# Kilobot_Controller_ISP.net
KiCad netlist of a schematic drawn in Altium Designer
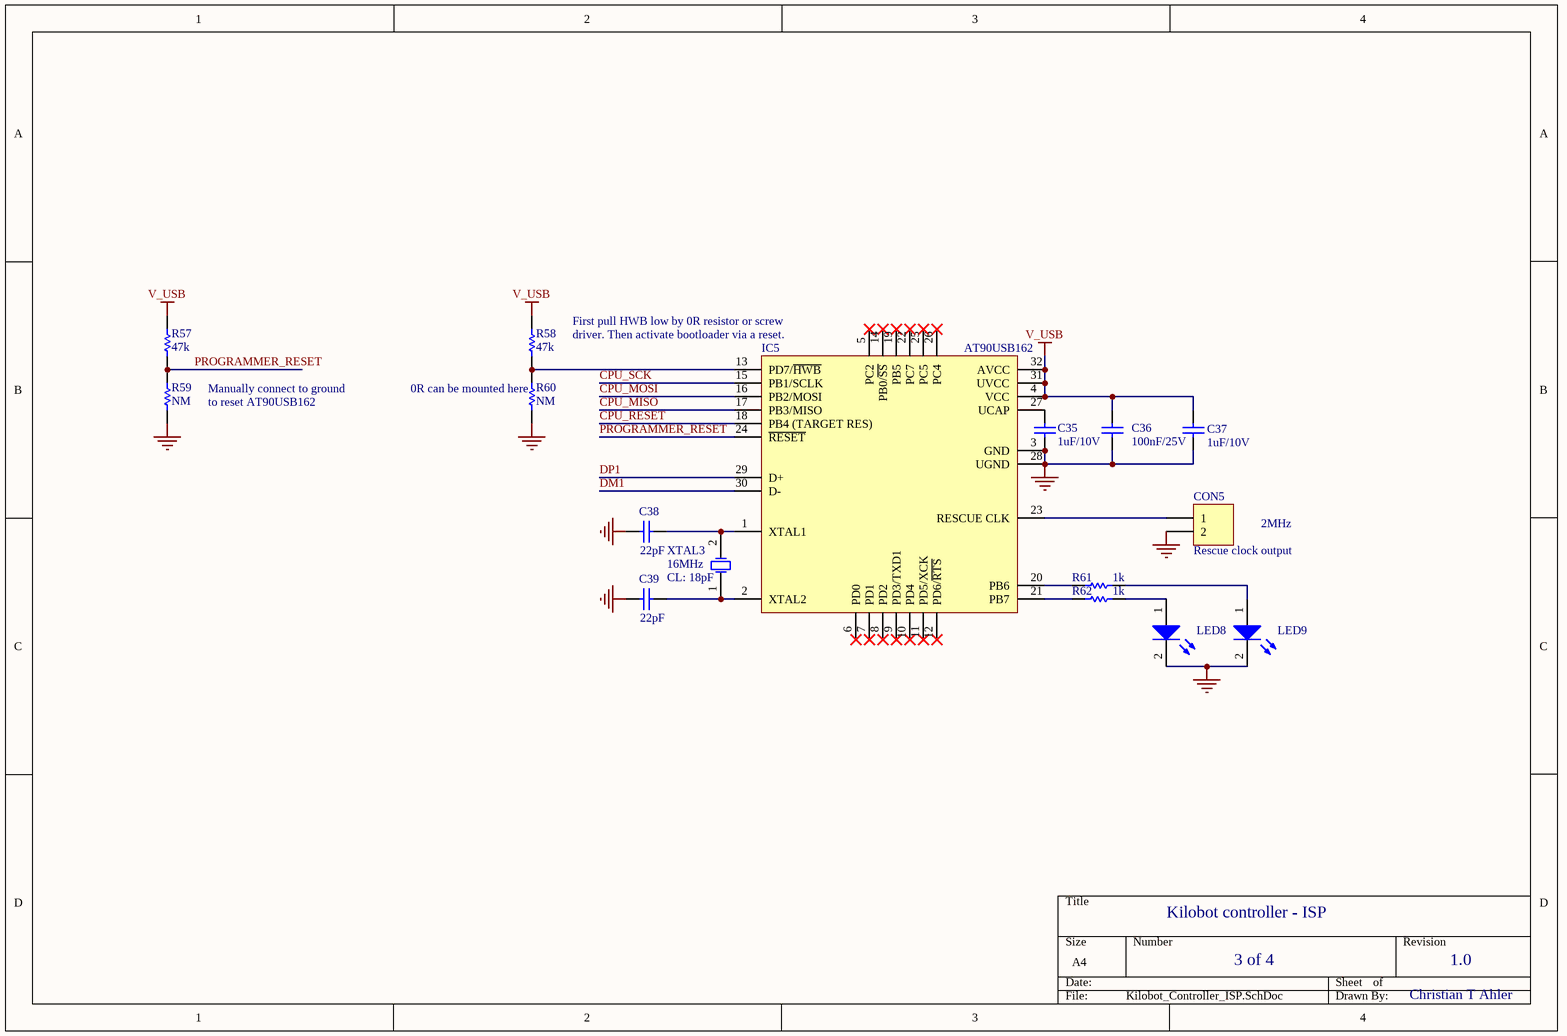
[diagram p0: Kilobot_Controller_ISP.SchDoc]

(export (version "E")
  (design (tool "Eeschema 10.0.6"))
  (components
    (comp (ref "C35")
      (value "1uF/10V")
      (footprint "RESC1608L")
      (description "Ceramic Chip Capacitor - Standard")
      (fields (field (name "Comment") "C0603"))
      (libsource (lib "KEMET Chip Capacitor") (part "C0603"))
    )
    (comp (ref "C36")
      (value "100nF/25V")
      (footprint "RESC1608L")
      (description "Ceramic Chip Capacitor - Standard")
      (fields (field (name "Comment") "C0603"))
      (libsource (lib "KEMET Chip Capacitor") (part "C0603"))
    )
    (comp (ref "C37")
      (value "1uF/10V")
      (footprint "RESC1608L")
      (description "Ceramic Chip Capacitor - Standard")
      (fields (field (name "Comment") "C0603"))
      (libsource (lib "KEMET Chip Capacitor") (part "C0603"))
    )
    (comp (ref "C38")
      (value "22pF")
      (footprint "RESC1608L")
      (description "Ceramic Chip Capacitor - Standard")
      (fields (field (name "Comment") "C0603"))
      (libsource (lib "KEMET Chip Capacitor") (part "C0603"))
    )
    (comp (ref "C39")
      (value "22pF")
      (footprint "RESC1608L")
      (description "Ceramic Chip Capacitor - Standard")
      (fields (field (name "Comment") "C0603"))
      (libsource (lib "KEMET Chip Capacitor") (part "C0603"))
    )
    (comp (ref "CON5")
      (value "Rescue clock output")
      (footprint "HDR1X2")
      (description "Header, 2-Pin")
      (libsource (lib "Miscellaneous Connectors") (part "Header 2"))
    )
    (comp (ref "IC5")
      (value "AT90USB162")
      (footprint "TQFP32")
      (libsource (lib "Kilobot_Controller") (part "AT90USB162"))
    )
    (comp (ref "LED8") (value "LED") (footprint "LED0603") (libsource (lib "KilobotCommercial") (part "LED")))
    (comp (ref "LED9") (value "LED") (footprint "LED0603") (libsource (lib "KilobotCommercial") (part "LED")))
    (comp (ref "R57")
      (value "47k")
      (footprint "RESC1608L")
      (description "Resistor")
      (fields (field (name "Comment") "Res1"))
      (libsource (lib "Miscellaneous Devices") (part "Res1"))
    )
    (comp (ref "R58")
      (value "47k")
      (footprint "RESC1608L")
      (description "Resistor")
      (fields (field (name "Comment") "Res1"))
      (libsource (lib "Miscellaneous Devices") (part "Res1"))
    )
    (comp (ref "R59")
      (value "NM")
      (footprint "RESC1608L")
      (description "Resistor")
      (fields (field (name "Comment") "Res1"))
      (libsource (lib "Miscellaneous Devices") (part "Res1"))
    )
    (comp (ref "R60")
      (value "NM")
      (footprint "RESC1608L")
      (description "Resistor")
      (fields (field (name "Comment") "Res1"))
      (libsource (lib "Miscellaneous Devices") (part "Res1"))
    )
    (comp (ref "R61")
      (value "1k")
      (footprint "RESC1608L")
      (description "Resistor")
      (fields (field (name "Comment") "Res1"))
      (libsource (lib "Miscellaneous Devices") (part "Res1"))
    )
    (comp (ref "R62")
      (value "1k")
      (footprint "RESC1608L")
      (description "Resistor")
      (fields (field (name "Comment") "Res1"))
      (libsource (lib "Miscellaneous Devices") (part "Res1"))
    )
    (comp (ref "XTAL3")
      (value "16MHz")
      (footprint "crystal-hc49")
      (fields (field (name "CL") "18pF") (field (name "Comment") "Crystal"))
      (libsource (lib "Programmer") (part "Crystal"))
    )
  )
  (nets
    (net (code "1") (name "/CPU_MISO") (class "Default")
      (node (ref "IC5") (pin "17") (pinfunction "PB3/MISO_17") (pintype "passive"))
    )
    (net (code "2") (name "/CPU_MOSI") (class "Default")
      (node (ref "IC5") (pin "16") (pinfunction "PB2/MOSI_16") (pintype "passive"))
    )
    (net (code "3") (name "/CPU_RESET") (class "Default")
      (node (ref "IC5") (pin "18") (pinfunction "PB4_(TARGET_RES)_18") (pintype "passive"))
    )
    (net (code "4") (name "/CPU_SCK") (class "Default")
      (node (ref "IC5") (pin "15") (pinfunction "PB1/SCLK_15") (pintype "passive"))
    )
    (net (code "5") (name "/DM1") (class "Default")
      (node (ref "IC5") (pin "30") (pinfunction "D-_30") (pintype "passive"))
    )
    (net (code "6") (name "/DP1") (class "Default")
      (node (ref "IC5") (pin "29") (pinfunction "D+_29") (pintype "passive"))
    )
    (net (code "7") (name "/PROGRAMMER_RESET") (class "Default")
      (node (ref "IC5") (pin "24") (pinfunction "~{RESET}_24") (pintype "passive"))
      (node (ref "R57") (pin "2") (pinfunction "2_2") (pintype "passive"))
      (node (ref "R59") (pin "1") (pinfunction "1_1") (pintype "passive"))
    )
    (net (code "8") (name "GND") (class "Default")
      (node (ref "C35") (pin "1") (pinfunction "1_1") (pintype "passive"))
      (node (ref "C36") (pin "2") (pinfunction "2_2") (pintype "passive"))
      (node (ref "C37") (pin "1") (pinfunction "1_1") (pintype "passive"))
      (node (ref "C38") (pin "1") (pinfunction "1_1") (pintype "passive"))
      (node (ref "C39") (pin "1") (pinfunction "1_1") (pintype "passive"))
      (node (ref "CON5") (pin "2") (pinfunction "2_2") (pintype "passive"))
      (node (ref "IC5") (pin "28") (pinfunction "UGND_28") (pintype "passive"))
      (node (ref "IC5") (pin "3") (pinfunction "GND_3") (pintype "passive"))
      (node (ref "LED8") (pin "2") (pinfunction "K_2") (pintype "passive"))
      (node (ref "LED9") (pin "2") (pinfunction "K_2") (pintype "passive"))
      (node (ref "R59") (pin "2") (pinfunction "2_2") (pintype "passive"))
      (node (ref "R60") (pin "2") (pinfunction "2_2") (pintype "passive"))
    )
    (net (code "9") (name "Net-(IC5-PB6)") (class "Default")
      (node (ref "IC5") (pin "20") (pinfunction "PB6_20") (pintype "passive"))
      (node (ref "R61") (pin "2") (pinfunction "2_2") (pintype "passive"))
    )
    (net (code "10") (name "Net-(IC5-PB7)") (class "Default")
      (node (ref "IC5") (pin "21") (pinfunction "PB7_21") (pintype "passive"))
      (node (ref "R62") (pin "2") (pinfunction "2_2") (pintype "passive"))
    )
    (net (code "11") (name "Net-(IC5-PD7{slash}~{HWB})") (class "Default")
      (node (ref "IC5") (pin "13") (pinfunction "PD7/~{HWB}_13") (pintype "passive"))
      (node (ref "R58") (pin "2") (pinfunction "2_2") (pintype "passive"))
      (node (ref "R60") (pin "1") (pinfunction "1_1") (pintype "passive"))
    )
    (net (code "12") (name "Net-(IC5-RESCUE_CLK)") (class "Default")
      (node (ref "CON5") (pin "1") (pinfunction "1_1") (pintype "passive"))
      (node (ref "IC5") (pin "23") (pinfunction "RESCUE_CLK_23") (pintype "passive"))
    )
    (net (code "13") (name "Net-(IC5-UCAP)") (class "Default")
      (node (ref "C35") (pin "2") (pinfunction "2_2") (pintype "passive"))
      (node (ref "IC5") (pin "27") (pinfunction "UCAP_27") (pintype "passive"))
    )
    (net (code "14") (name "Net-(IC5-XTAL1)") (class "Default")
      (node (ref "C38") (pin "2") (pinfunction "2_2") (pintype "passive"))
      (node (ref "IC5") (pin "1") (pinfunction "XTAL1_1") (pintype "passive"))
      (node (ref "XTAL3") (pin "2") (pinfunction "OSC2_2") (pintype "passive"))
    )
    (net (code "15") (name "Net-(IC5-XTAL2)") (class "Default")
      (node (ref "C39") (pin "2") (pinfunction "2_2") (pintype "passive"))
      (node (ref "IC5") (pin "2") (pinfunction "XTAL2_2") (pintype "passive"))
      (node (ref "XTAL3") (pin "1") (pinfunction "OSC1_1") (pintype "passive"))
    )
    (net (code "16") (name "Net-(LED8-A)") (class "Default")
      (node (ref "LED8") (pin "1") (pinfunction "A_1") (pintype "passive"))
      (node (ref "R62") (pin "1") (pinfunction "1_1") (pintype "passive"))
    )
    (net (code "17") (name "Net-(LED9-A)") (class "Default")
      (node (ref "LED9") (pin "1") (pinfunction "A_1") (pintype "passive"))
      (node (ref "R61") (pin "1") (pinfunction "1_1") (pintype "passive"))
    )
    (net (code "18") (name "V_USB") (class "Default")
      (node (ref "C36") (pin "1") (pinfunction "1_1") (pintype "passive"))
      (node (ref "C37") (pin "2") (pinfunction "2_2") (pintype "passive"))
      (node (ref "IC5") (pin "31") (pinfunction "UVCC_31") (pintype "passive"))
      (node (ref "IC5") (pin "32") (pinfunction "AVCC_32") (pintype "passive"))
      (node (ref "IC5") (pin "4") (pinfunction "VCC_4") (pintype "passive"))
      (node (ref "R57") (pin "1") (pinfunction "1_1") (pintype "passive"))
      (node (ref "R58") (pin "1") (pinfunction "1_1") (pintype "passive"))
    )
    (net (code "19") (name "unconnected-(IC5-PB0{slash}~{SS}-Pad14)") (class "Default")
      (node (ref "IC5") (pin "14") (pinfunction "PB0/~{SS}_14") (pintype "passive+no_connect"))
    )
    (net (code "20") (name "unconnected-(IC5-PB5-Pad19)") (class "Default")
      (node (ref "IC5") (pin "19") (pinfunction "PB5_19") (pintype "passive+no_connect"))
    )
    (net (code "21") (name "unconnected-(IC5-PC2-Pad5)") (class "Default")
      (node (ref "IC5") (pin "5") (pinfunction "PC2_5") (pintype "passive+no_connect"))
    )
    (net (code "22") (name "unconnected-(IC5-PC4-Pad26)") (class "Default")
      (node (ref "IC5") (pin "26") (pinfunction "PC4_26") (pintype "passive+no_connect"))
    )
    (net (code "23") (name "unconnected-(IC5-PC5-Pad25)") (class "Default")
      (node (ref "IC5") (pin "25") (pinfunction "PC5_25") (pintype "passive+no_connect"))
    )
    (net (code "24") (name "unconnected-(IC5-PC7-Pad22)") (class "Default")
      (node (ref "IC5") (pin "22") (pinfunction "PC7_22") (pintype "passive+no_connect"))
    )
    (net (code "25") (name "unconnected-(IC5-PD0-Pad6)") (class "Default")
      (node (ref "IC5") (pin "6") (pinfunction "PD0_6") (pintype "passive+no_connect"))
    )
    (net (code "26") (name "unconnected-(IC5-PD1-Pad7)") (class "Default")
      (node (ref "IC5") (pin "7") (pinfunction "PD1_7") (pintype "passive+no_connect"))
    )
    (net (code "27") (name "unconnected-(IC5-PD2-Pad8)") (class "Default")
      (node (ref "IC5") (pin "8") (pinfunction "PD2_8") (pintype "passive+no_connect"))
    )
    (net (code "28") (name "unconnected-(IC5-PD3{slash}TXD1-Pad9)") (class "Default")
      (node (ref "IC5") (pin "9") (pinfunction "PD3/TXD1_9") (pintype "passive+no_connect"))
    )
    (net (code "29") (name "unconnected-(IC5-PD4-Pad10)") (class "Default")
      (node (ref "IC5") (pin "10") (pinfunction "PD4_10") (pintype "passive+no_connect"))
    )
    (net (code "30") (name "unconnected-(IC5-PD5{slash}XCK-Pad11)") (class "Default")
      (node (ref "IC5") (pin "11") (pinfunction "PD5/XCK_11") (pintype "passive+no_connect"))
    )
    (net (code "31") (name "unconnected-(IC5-PD6{slash}~{RTS}-Pad12)") (class "Default")
      (node (ref "IC5") (pin "12") (pinfunction "PD6/~{RTS}_12") (pintype "passive+no_connect"))
    )
  )
)
